# QREx4.net
KiCad netlist of a schematic drawn in EAGLE
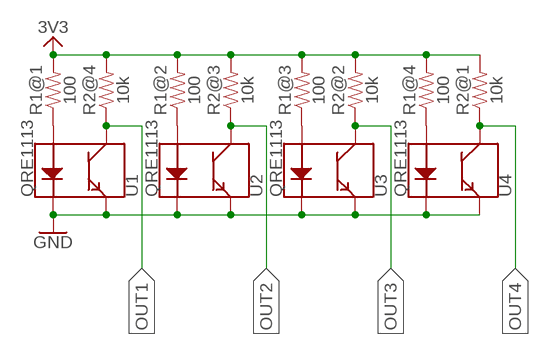
[diagram p0: schematic, sheet 1]

(export (version "E")
  (design (tool "Eeschema 10.0.6"))
  (components
    (comp (ref "R1")
      (value "100")
      (footprint "eagle-import:RESCAF80P320X160X60-8N")
      (libsource (lib "eagle-import") (part "RESISTOR_ARRAY_1206_SEPARATE"))
    )
    (comp (ref "R2")
      (value "10k")
      (footprint "eagle-import:RESCAF80P320X160X60-8N")
      (libsource (lib "eagle-import") (part "RESISTOR_ARRAY_1206_SEPARATE"))
    )
    (comp (ref "U1")
      (value "QRE1113")
      (footprint "eagle-import:QRE1113-W")
      (libsource (lib "eagle-import") (part "QRE1113SMD-W"))
    )
    (comp (ref "U2")
      (value "QRE1113")
      (footprint "eagle-import:QRE1113-W")
      (libsource (lib "eagle-import") (part "QRE1113SMD-W"))
    )
    (comp (ref "U3")
      (value "QRE1113")
      (footprint "eagle-import:QRE1113-W")
      (libsource (lib "eagle-import") (part "QRE1113SMD-W"))
    )
    (comp (ref "U4")
      (value "QRE1113")
      (footprint "eagle-import:QRE1113-W")
      (libsource (lib "eagle-import") (part "QRE1113SMD-W"))
    )
  )
  (nets
    (net (code "1") (name "Net-(R1B-1)") (class "Default")
      (node (ref "R1") (pin "2") (pinfunction "1_2") (pintype "passive"))
      (node (ref "U2") (pin "1") (pinfunction "A_1") (pintype "bidirectional"))
    )
    (net (code "2") (name "Net-(R1C-1)") (class "Default")
      (node (ref "R1") (pin "3") (pinfunction "1_3") (pintype "passive"))
      (node (ref "U3") (pin "1") (pinfunction "A_1") (pintype "bidirectional"))
    )
    (net (code "3") (name "Net-(R1D-1)") (class "Default")
      (node (ref "R1") (pin "4") (pinfunction "1_4") (pintype "passive"))
      (node (ref "U4") (pin "1") (pinfunction "A_1") (pintype "bidirectional"))
    )
    (net (code "4") (name "Net-(U1-A)") (class "Default")
      (node (ref "R1") (pin "1") (pinfunction "1_1") (pintype "passive"))
      (node (ref "U1") (pin "1") (pinfunction "A_1") (pintype "bidirectional"))
    )
    (net (code "5") (name "OUT1") (class "Default")
      (node (ref "R2") (pin "4") (pinfunction "1_4") (pintype "passive"))
      (node (ref "U1") (pin "3") (pinfunction "C_3") (pintype "bidirectional"))
    )
    (net (code "6") (name "OUT2") (class "Default")
      (node (ref "R2") (pin "3") (pinfunction "1_3") (pintype "passive"))
      (node (ref "U2") (pin "3") (pinfunction "C_3") (pintype "bidirectional"))
    )
    (net (code "7") (name "OUT3") (class "Default")
      (node (ref "R2") (pin "2") (pinfunction "1_2") (pintype "passive"))
      (node (ref "U3") (pin "3") (pinfunction "C_3") (pintype "bidirectional"))
    )
    (net (code "8") (name "OUT4") (class "Default")
      (node (ref "R2") (pin "1") (pinfunction "1_1") (pintype "passive"))
      (node (ref "U4") (pin "3") (pinfunction "C_3") (pintype "bidirectional"))
    )
    (net (code "9") (name "SUPPLY_3.3V") (class "Default")
      (node (ref "R1") (pin "5") (pinfunction "2_5") (pintype "passive"))
      (node (ref "R1") (pin "6") (pinfunction "2_6") (pintype "passive"))
      (node (ref "R1") (pin "7") (pinfunction "2_7") (pintype "passive"))
      (node (ref "R1") (pin "8") (pinfunction "2_8") (pintype "passive"))
      (node (ref "R2") (pin "5") (pinfunction "2_5") (pintype "passive"))
      (node (ref "R2") (pin "6") (pinfunction "2_6") (pintype "passive"))
      (node (ref "R2") (pin "7") (pinfunction "2_7") (pintype "passive"))
      (node (ref "R2") (pin "8") (pinfunction "2_8") (pintype "passive"))
    )
    (net (code "10") (name "SUPPLY_GND") (class "Default")
      (node (ref "U1") (pin "2") (pinfunction "K_2") (pintype "bidirectional"))
      (node (ref "U1") (pin "4") (pinfunction "E_4") (pintype "bidirectional"))
      (node (ref "U2") (pin "2") (pinfunction "K_2") (pintype "bidirectional"))
      (node (ref "U2") (pin "4") (pinfunction "E_4") (pintype "bidirectional"))
      (node (ref "U3") (pin "2") (pinfunction "K_2") (pintype "bidirectional"))
      (node (ref "U3") (pin "4") (pinfunction "E_4") (pintype "bidirectional"))
      (node (ref "U4") (pin "2") (pinfunction "K_2") (pintype "bidirectional"))
      (node (ref "U4") (pin "4") (pinfunction "E_4") (pintype "bidirectional"))
    )
  )
)
